# rele.net
KiCad netlist of a schematic drawn in Altium Designer
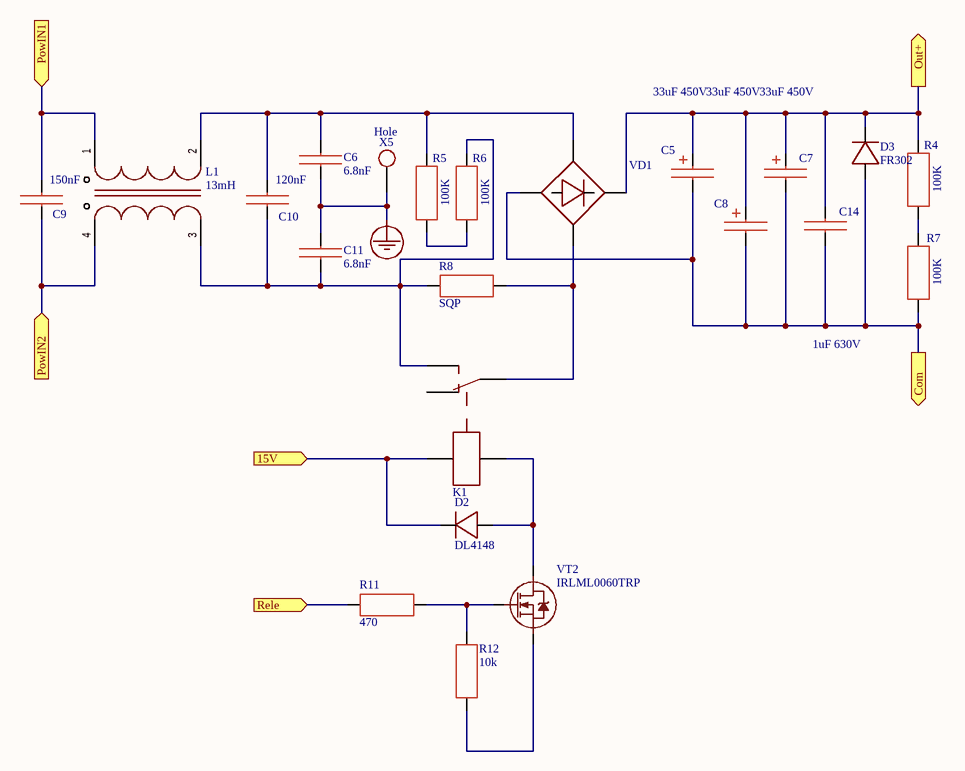
[diagram p0: rele.SchDoc]

(export (version "E")
  (design (tool "Eeschema 10.0.6"))
  (components
    (comp (ref "C5")
      (value "33uF 450V")
      (footprint "K50-35_oll_models:D16_F7.5_d0.8_31.5")
      (libsource (lib "K50-35_oll_models") (part "33uF 450V"))
    )
    (comp (ref "C6")
      (value "6.8nF")
      (footprint "B3202X:10_5_11_13")
      (libsource (lib "B3202X") (part "B32021-10mm-6.8nF"))
    )
    (comp (ref "C7")
      (value "33uF 450V")
      (footprint "K50-35_oll_models:D16_F7.5_d0.8_31.5")
      (libsource (lib "K50-35_oll_models") (part "33uF 450V"))
    )
    (comp (ref "C8")
      (value "33uF 450V")
      (footprint "K50-35_oll_models:D16_F7.5_d0.8_31.5")
      (libsource (lib "K50-35_oll_models") (part "33uF 450V"))
    )
    (comp (ref "C9")
      (value "150nF")
      (footprint "MKP_Capacitor:case M")
      (libsource (lib "MKP_Capacitor") (part "MKP63 case_M"))
    )
    (comp (ref "C10")
      (value "120nF")
      (footprint "MKP_Capacitor:case M")
      (libsource (lib "MKP_Capacitor") (part "MKP63 case_M"))
    )
    (comp (ref "C11")
      (value "6.8nF")
      (footprint "B3202X:10_5_11_13")
      (libsource (lib "B3202X") (part "B32021-10mm-6.8nF"))
    )
    (comp (ref "C14")
      (value "1uF 630V")
      (footprint "29_22,5_13,5_27,5_0,8")
      (libsource (lib "CBB21") (part "1uF 630V"))
    )
    (comp (ref "D2") (value "DL4148") (footprint "DL4148:DL-35") (libsource (lib "DL4148") (part "DL4148")))
    (comp (ref "D3") (value "FR302") (footprint "DO-27-V") (libsource (lib "FR302") (part "FR302")))
    (comp (ref "K1") (value "Relay") (footprint "1C") (libsource (lib "833H-1C") (part "833H")))
    (comp (ref "L1")
      (value "13mH")
      (footprint "PLA10AS1330R5D2B:PLA10")
      (libsource (lib "PLA10AS1330R5D2B") (part "PLA10AS1330R5D2B"))
    )
    (comp (ref "R4")
      (value "100K")
      (footprint "Resistor:RC1206")
      (libsource (lib "Resistor") (part "RC1206 X Ohm"))
    )
    (comp (ref "R5")
      (value "100K")
      (footprint "Resistor:RC1206")
      (libsource (lib "Resistor") (part "RC1206 X Ohm"))
    )
    (comp (ref "R6")
      (value "100K")
      (footprint "Resistor:RC1206")
      (libsource (lib "Resistor") (part "RC1206 X Ohm"))
    )
    (comp (ref "R7")
      (value "100K")
      (footprint "Resistor:RC1206")
      (libsource (lib "Resistor") (part "RC1206 X Ohm"))
    )
    (comp (ref "R8") (value "SQP") (footprint "SQP:5W") (libsource (lib "SQP") (part "SQP")))
    (comp (ref "R11")
      (value "470")
      (footprint "Resistor:RC0805_3D")
      (libsource (lib "Resistor") (part "RC0805 X Ohm"))
    )
    (comp (ref "R12")
      (value "10k")
      (footprint "Resistor:RC0805_3D")
      (libsource (lib "Resistor") (part "RC0805 X Ohm"))
    )
    (comp (ref "VD1")
      (value "KBU1010")
      (footprint "KBU1010:KBU")
      (libsource (lib "KBU1010") (part "KBU1010"))
    )
    (comp (ref "VT2")
      (value "IRLML0060TRP")
      (footprint "SOT23")
      (libsource (lib "IR Mosfet") (part "IRLML0060TRP"))
    )
    (comp (ref "X5") (value "Hole") (footprint "Round_3x1.2") (libsource (lib "Hole") (part "Hole")))
  )
  (nets
    (net (code "1") (name "/15V") (class "Default")
      (node (ref "D2") (pin "1") (pinfunction "1_1") (pintype "passive"))
      (node (ref "K1") (pin "1") (pinfunction "1_1") (pintype "passive"))
    )
    (net (code "2") (name "/Com") (class "Default")
      (node (ref "C14") (pin "2") (pinfunction "2_2") (pintype "passive"))
      (node (ref "C5") (pin "2") (pinfunction "2_2") (pintype "passive"))
      (node (ref "C7") (pin "2") (pinfunction "2_2") (pintype "passive"))
      (node (ref "C8") (pin "2") (pinfunction "2_2") (pintype "passive"))
      (node (ref "D3") (pin "1") (pinfunction "A_1") (pintype "passive"))
      (node (ref "R7") (pin "1") (pinfunction "1_1") (pintype "passive"))
      (node (ref "VD1") (pin "4") (pinfunction "4_4") (pintype "passive"))
    )
    (net (code "3") (name "/Out+") (class "Default")
      (node (ref "C14") (pin "1") (pinfunction "1_1") (pintype "passive"))
      (node (ref "C5") (pin "1") (pinfunction "1_1") (pintype "passive"))
      (node (ref "C7") (pin "1") (pinfunction "1_1") (pintype "passive"))
      (node (ref "C8") (pin "1") (pinfunction "1_1") (pintype "passive"))
      (node (ref "D3") (pin "2") (pinfunction "K_2") (pintype "passive"))
      (node (ref "R4") (pin "2") (pinfunction "2_2") (pintype "passive"))
      (node (ref "VD1") (pin "1") (pinfunction "1_1") (pintype "passive"))
    )
    (net (code "4") (name "/PowIN1") (class "Default")
      (node (ref "C9") (pin "2") (pinfunction "2_2") (pintype "passive"))
      (node (ref "L1") (pin "1") (pinfunction "1_1") (pintype "passive"))
    )
    (net (code "5") (name "/PowIN2") (class "Default")
      (node (ref "C9") (pin "1") (pinfunction "1_1") (pintype "passive"))
      (node (ref "L1") (pin "4") (pinfunction "4_4") (pintype "passive"))
    )
    (net (code "6") (name "/Rele") (class "Default")
      (node (ref "R11") (pin "2") (pinfunction "2_2") (pintype "passive"))
    )
    (net (code "7") (name "GND_B") (class "Default")
      (node (ref "C11") (pin "2") (pinfunction "2_2") (pintype "passive"))
      (node (ref "C6") (pin "1") (pinfunction "1_1") (pintype "passive"))
      (node (ref "X5") (pin "1") (pinfunction "1_1") (pintype "passive"))
    )
    (net (code "8") (name "Net-(C10-Pad1)") (class "Default")
      (node (ref "C10") (pin "1") (pinfunction "1_1") (pintype "passive"))
      (node (ref "C11") (pin "1") (pinfunction "1_1") (pintype "passive"))
      (node (ref "K1") (pin "3") (pinfunction "3_3") (pintype "passive"))
      (node (ref "L1") (pin "3") (pinfunction "3_3") (pintype "passive"))
      (node (ref "R6") (pin "2") (pinfunction "2_2") (pintype "passive"))
      (node (ref "R8") (pin "1") (pinfunction "1_1") (pintype "passive"))
    )
    (net (code "9") (name "Net-(C10-Pad2)") (class "Default")
      (node (ref "C10") (pin "2") (pinfunction "2_2") (pintype "passive"))
      (node (ref "C6") (pin "2") (pinfunction "2_2") (pintype "passive"))
      (node (ref "L1") (pin "2") (pinfunction "2_2") (pintype "passive"))
      (node (ref "R5") (pin "2") (pinfunction "2_2") (pintype "passive"))
      (node (ref "VD1") (pin "3") (pinfunction "3_3") (pintype "passive"))
    )
    (net (code "10") (name "Net-(D2-Pad2)") (class "Default")
      (node (ref "D2") (pin "2") (pinfunction "2_2") (pintype "passive"))
      (node (ref "K1") (pin "4") (pinfunction "4_4") (pintype "passive"))
      (node (ref "VT2") (pin "3") (pinfunction "3_3") (pintype "passive"))
    )
    (net (code "11") (name "Net-(K1-Pad5)") (class "Default")
      (node (ref "K1") (pin "5") (pinfunction "5_5") (pintype "passive"))
      (node (ref "R8") (pin "2") (pinfunction "2_2") (pintype "passive"))
      (node (ref "VD1") (pin "2") (pinfunction "2_2") (pintype "passive"))
    )
    (net (code "12") (name "Net-(R4-Pad1)") (class "Default")
      (node (ref "R4") (pin "1") (pinfunction "1_1") (pintype "passive"))
      (node (ref "R7") (pin "2") (pinfunction "2_2") (pintype "passive"))
    )
    (net (code "13") (name "Net-(R5-Pad1)") (class "Default")
      (node (ref "R5") (pin "1") (pinfunction "1_1") (pintype "passive"))
      (node (ref "R6") (pin "1") (pinfunction "1_1") (pintype "passive"))
    )
    (net (code "14") (name "Net-(R11-Pad1)") (class "Default")
      (node (ref "R11") (pin "1") (pinfunction "1_1") (pintype "passive"))
      (node (ref "R12") (pin "1") (pinfunction "1_1") (pintype "passive"))
      (node (ref "VT2") (pin "1") (pinfunction "1_1") (pintype "passive"))
    )
    (net (code "15") (name "Net-(R12-Pad2)") (class "Default")
      (node (ref "R12") (pin "2") (pinfunction "2_2") (pintype "passive"))
      (node (ref "VT2") (pin "2") (pinfunction "2_2") (pintype "passive"))
    )
    (net (code "16") (name "unconnected-(K1-Pad2)") (class "Default")
      (node (ref "K1") (pin "2") (pinfunction "2_2") (pintype "passive"))
    )
  )
)
